# radio.net
KiCad netlist of a schematic drawn in Altium Designer
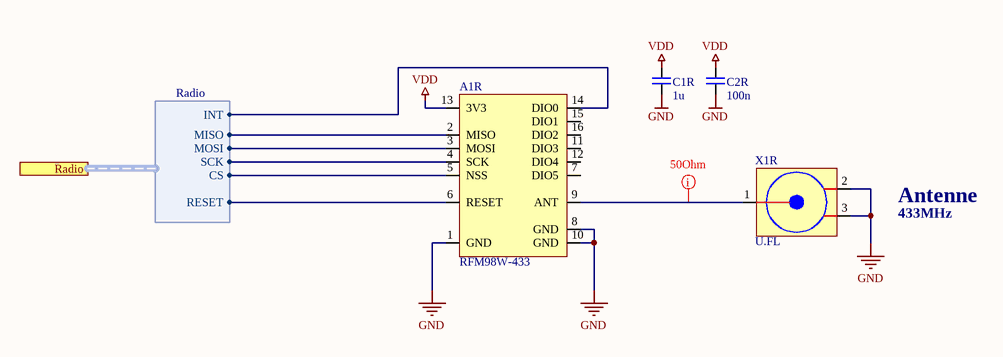
[diagram p0: radio.SchDoc]

(export (version "E")
  (design (tool "Eeschema 10.0.6"))
  (components
    (comp (ref "A1R")
      (value "RFM98W-433")
      (footprint "RFM98W")
      (description "LoRa Module\r\n433 MHz")
      (libsource (lib "Modules") (part "RFM98W"))
    )
    (comp (ref "C1R") (value "1u") (footprint "0805") (libsource (lib "Passive") (part "Kondensator")))
    (comp (ref "C2R") (value "100n") (footprint "0805") (libsource (lib "Passive") (part "Kondensator")))
    (comp (ref "X1R") (value "U.FL") (footprint "UFL") (libsource (lib "Connectors") (part "U.FL")))
  )
  (nets
    (net (code "2") (name "/CS") (class "Default")
      (node (ref "A1R") (pin "5") (pinfunction "NSS_5") (pintype "passive"))
    )
    (net (code "3") (name "/INT") (class "Default")
      (node (ref "A1R") (pin "14") (pinfunction "DIO0_14") (pintype "passive"))
    )
    (net (code "4") (name "/MISO") (class "Default")
      (node (ref "A1R") (pin "2") (pinfunction "MISO_2") (pintype "passive"))
    )
    (net (code "5") (name "/MOSI") (class "Default")
      (node (ref "A1R") (pin "3") (pinfunction "MOSI_3") (pintype "passive"))
    )
    (net (code "6") (name "/RESET") (class "Default")
      (node (ref "A1R") (pin "6") (pinfunction "RESET_6") (pintype "passive"))
    )
    (net (code "7") (name "/SCK") (class "Default")
      (node (ref "A1R") (pin "4") (pinfunction "SCK_4") (pintype "passive"))
    )
    (net (code "9") (name "GND") (class "Default")
      (node (ref "A1R") (pin "1") (pinfunction "GND_1") (pintype "passive"))
      (node (ref "A1R") (pin "10") (pinfunction "GND_10") (pintype "passive"))
      (node (ref "A1R") (pin "8") (pinfunction "GND_8") (pintype "passive"))
      (node (ref "C1R") (pin "1") (pinfunction "1_1") (pintype "passive"))
      (node (ref "C2R") (pin "1") (pinfunction "1_1") (pintype "passive"))
      (node (ref "X1R") (pin "2") (pinfunction "GND_2") (pintype "passive"))
      (node (ref "X1R") (pin "3") (pinfunction "GND_3") (pintype "passive"))
    )
    (net (code "10") (name "Net-(A1R-ANT)") (class "Default")
      (node (ref "A1R") (pin "9") (pinfunction "ANT_9") (pintype "passive"))
      (node (ref "X1R") (pin "1") (pinfunction "Signal_1") (pintype "passive"))
    )
    (net (code "11") (name "VDD") (class "Default")
      (node (ref "A1R") (pin "13") (pinfunction "3V3_13") (pintype "passive"))
      (node (ref "C1R") (pin "2") (pinfunction "2_2") (pintype "passive"))
      (node (ref "C2R") (pin "2") (pinfunction "2_2") (pintype "passive"))
    )
    (net (code "12") (name "unconnected-(A1R-DIO1-Pad15)") (class "Default")
      (node (ref "A1R") (pin "15") (pinfunction "DIO1_15") (pintype "passive"))
    )
    (net (code "13") (name "unconnected-(A1R-DIO2-Pad16)") (class "Default")
      (node (ref "A1R") (pin "16") (pinfunction "DIO2_16") (pintype "passive"))
    )
    (net (code "14") (name "unconnected-(A1R-DIO3-Pad11)") (class "Default")
      (node (ref "A1R") (pin "11") (pinfunction "DIO3_11") (pintype "passive"))
    )
    (net (code "15") (name "unconnected-(A1R-DIO4-Pad12)") (class "Default")
      (node (ref "A1R") (pin "12") (pinfunction "DIO4_12") (pintype "passive"))
    )
    (net (code "16") (name "unconnected-(A1R-DIO5-Pad7)") (class "Default")
      (node (ref "A1R") (pin "7") (pinfunction "DIO5_7") (pintype "passive"))
    )
  )
)
